# LEDs.net
KiCad netlist of a schematic drawn in Altium Designer
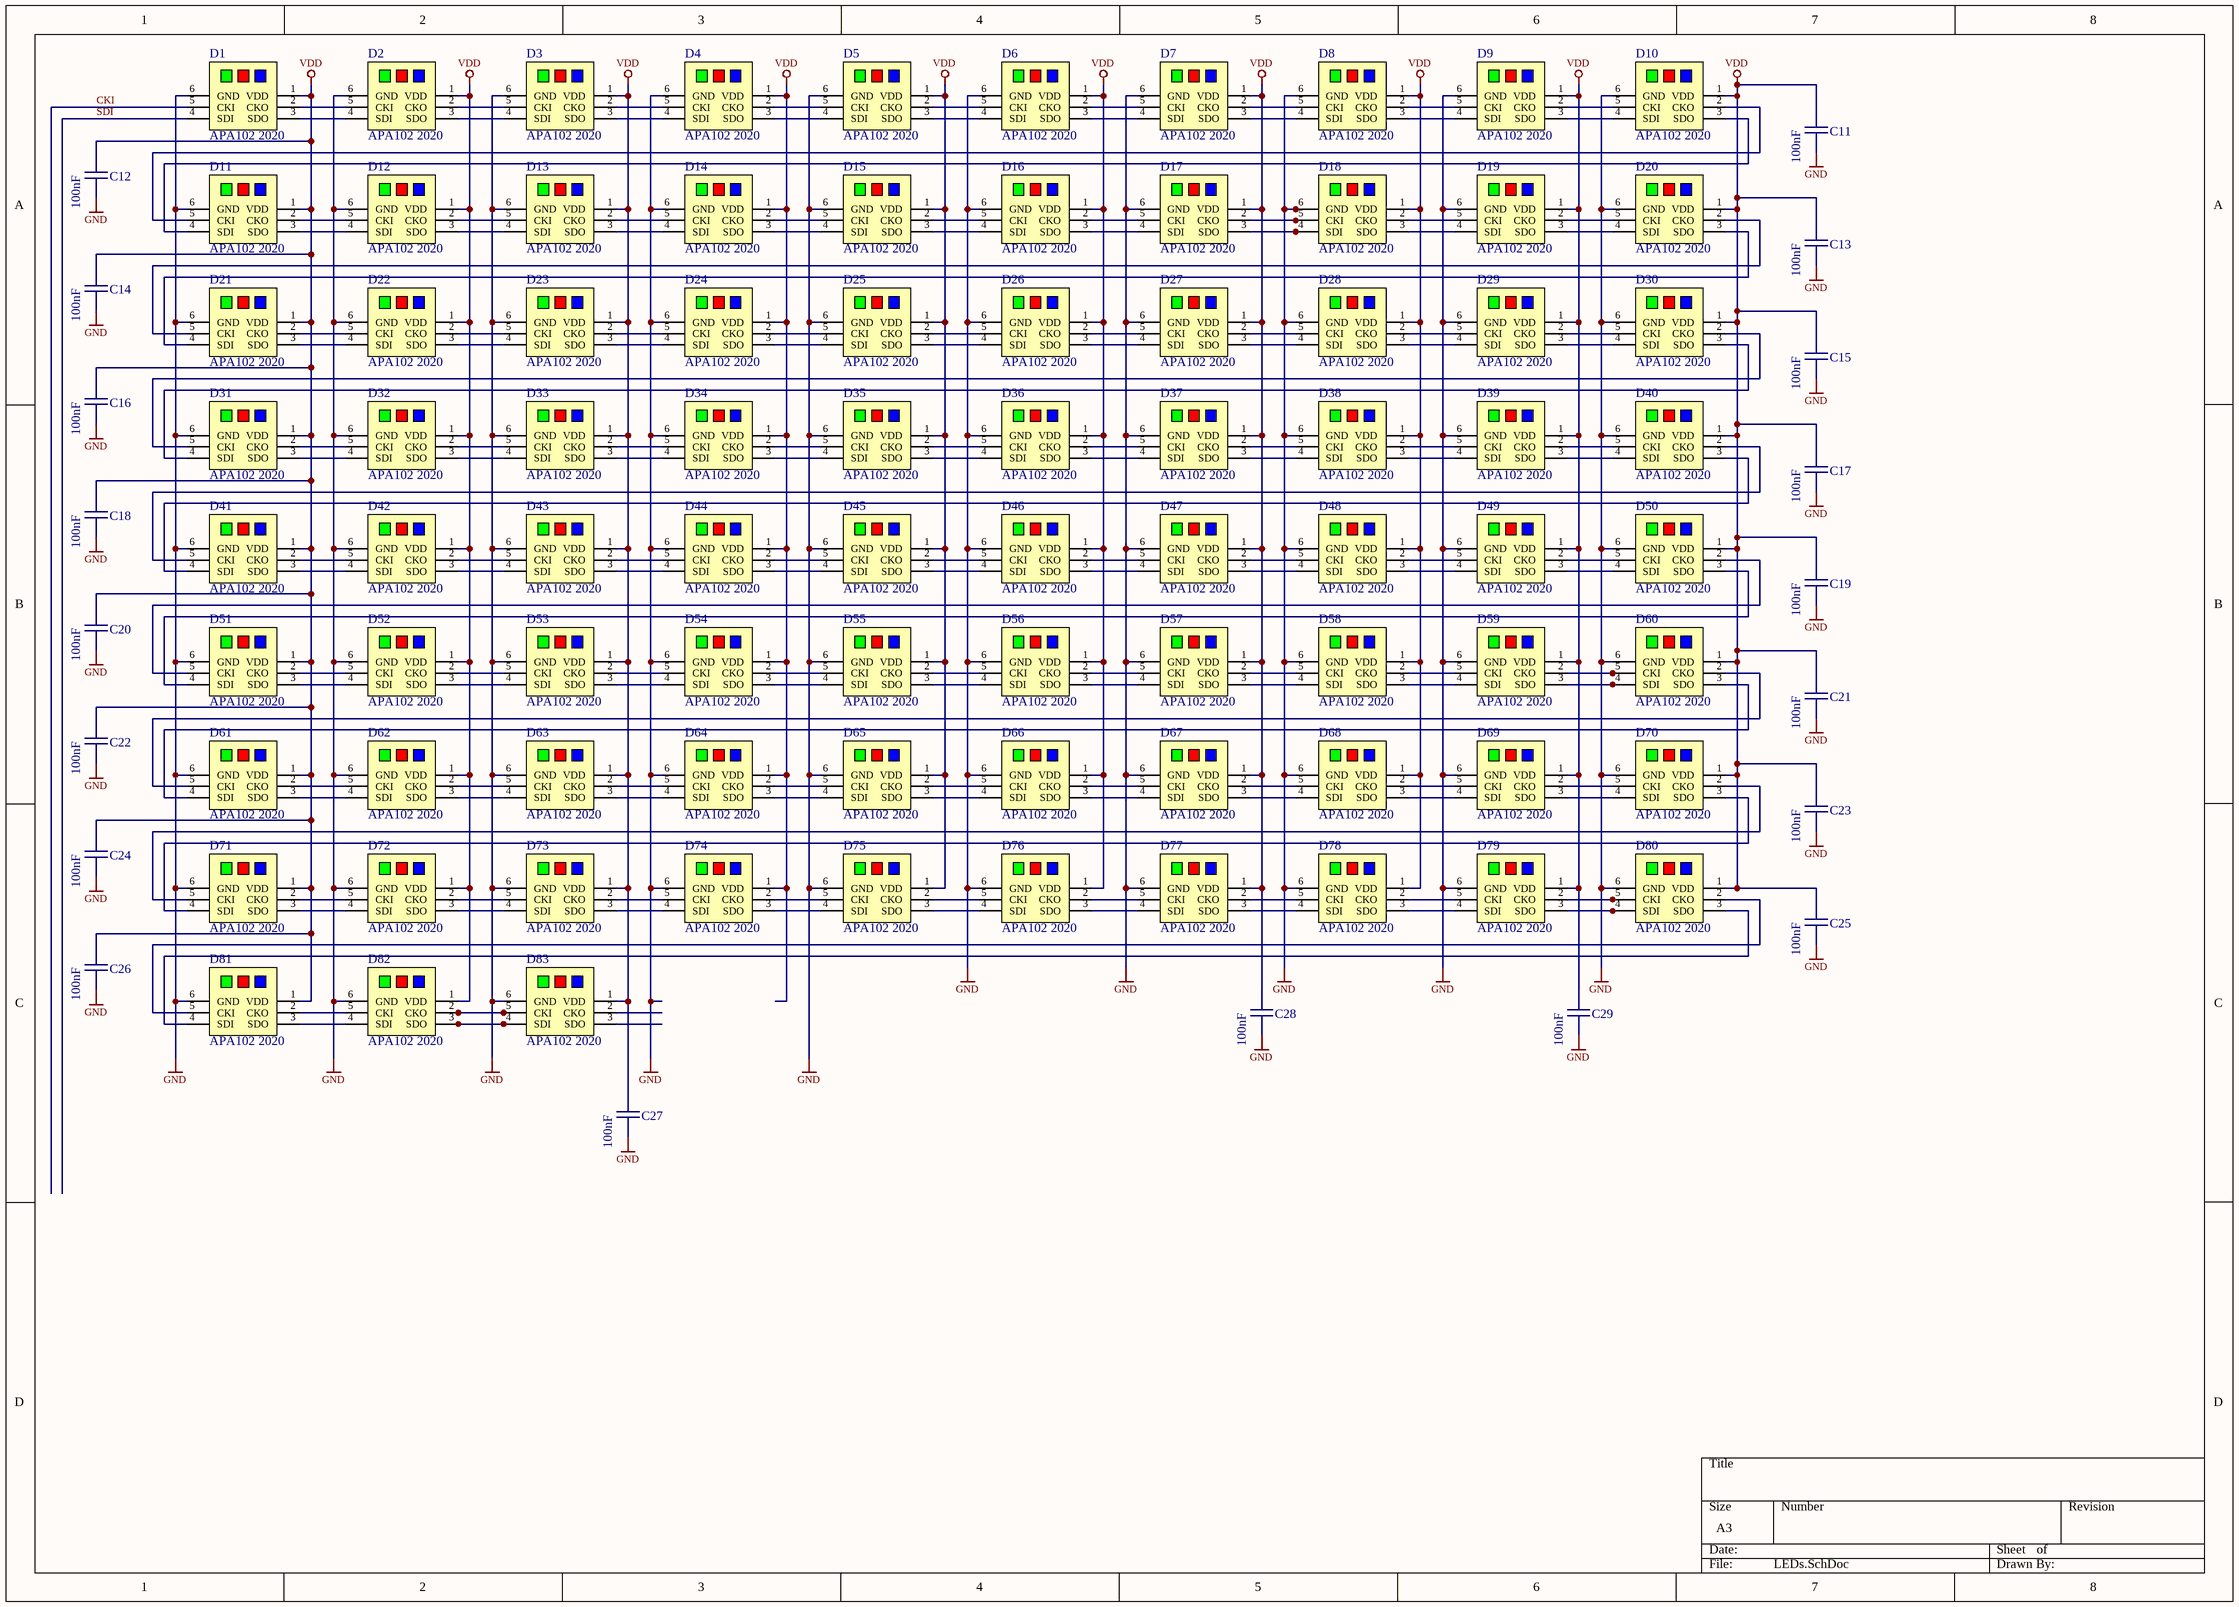
[diagram p0: LEDs.SchDoc]

(export (version "E")
  (design (tool "Eeschema 10.0.6"))
  (components
    (comp (ref "C11")
      (value "100nF")
      (footprint "CAPC0603(1608)55_N")
      (libsource (lib "OVLib_64") (part "CAP"))
    )
    (comp (ref "C12")
      (value "100nF")
      (footprint "CAPC0603(1608)55_N")
      (libsource (lib "OVLib_64") (part "CAP"))
    )
    (comp (ref "C13")
      (value "100nF")
      (footprint "CAPC0603(1608)55_N")
      (libsource (lib "OVLib_64") (part "CAP"))
    )
    (comp (ref "C14")
      (value "100nF")
      (footprint "CAPC0603(1608)55_N")
      (libsource (lib "OVLib_64") (part "CAP"))
    )
    (comp (ref "C15")
      (value "100nF")
      (footprint "CAPC0603(1608)55_N")
      (libsource (lib "OVLib_64") (part "CAP"))
    )
    (comp (ref "C16")
      (value "100nF")
      (footprint "CAPC0603(1608)55_N")
      (libsource (lib "OVLib_64") (part "CAP"))
    )
    (comp (ref "C17")
      (value "100nF")
      (footprint "CAPC0603(1608)55_N")
      (libsource (lib "OVLib_64") (part "CAP"))
    )
    (comp (ref "C18")
      (value "100nF")
      (footprint "CAPC0603(1608)55_N")
      (libsource (lib "OVLib_64") (part "CAP"))
    )
    (comp (ref "C19")
      (value "100nF")
      (footprint "CAPC0603(1608)55_N")
      (libsource (lib "OVLib_64") (part "CAP"))
    )
    (comp (ref "C20")
      (value "100nF")
      (footprint "CAPC0603(1608)55_N")
      (libsource (lib "OVLib_64") (part "CAP"))
    )
    (comp (ref "C21")
      (value "100nF")
      (footprint "CAPC0603(1608)55_N")
      (libsource (lib "OVLib_64") (part "CAP"))
    )
    (comp (ref "C22")
      (value "100nF")
      (footprint "CAPC0603(1608)55_N")
      (libsource (lib "OVLib_64") (part "CAP"))
    )
    (comp (ref "C23")
      (value "100nF")
      (footprint "CAPC0603(1608)55_N")
      (libsource (lib "OVLib_64") (part "CAP"))
    )
    (comp (ref "C24")
      (value "100nF")
      (footprint "CAPC0603(1608)55_N")
      (libsource (lib "OVLib_64") (part "CAP"))
    )
    (comp (ref "C25")
      (value "100nF")
      (footprint "CAPC0603(1608)55_N")
      (libsource (lib "OVLib_64") (part "CAP"))
    )
    (comp (ref "C26")
      (value "100nF")
      (footprint "CAPC0603(1608)55_N")
      (libsource (lib "OVLib_64") (part "CAP"))
    )
    (comp (ref "C27")
      (value "100nF")
      (footprint "CAPC0603(1608)55_N")
      (libsource (lib "OVLib_64") (part "CAP"))
    )
    (comp (ref "C28")
      (value "100nF")
      (footprint "CAPC0603(1608)55_N")
      (libsource (lib "OVLib_64") (part "CAP"))
    )
    (comp (ref "C29")
      (value "100nF")
      (footprint "CAPC0603(1608)55_N")
      (libsource (lib "OVLib_64") (part "CAP"))
    )
    (comp (ref "D1")
      (value "APA102 2020")
      (footprint "APA_RGB_LED_2020")
      (libsource (lib "OVLib_64") (part "LED_RGB_APA102"))
    )
    (comp (ref "D2")
      (value "APA102 2020")
      (footprint "APA_RGB_LED_2020")
      (libsource (lib "OVLib_64") (part "LED_RGB_APA102"))
    )
    (comp (ref "D3")
      (value "APA102 2020")
      (footprint "APA_RGB_LED_2020")
      (libsource (lib "OVLib_64") (part "LED_RGB_APA102"))
    )
    (comp (ref "D4")
      (value "APA102 2020")
      (footprint "APA_RGB_LED_2020")
      (libsource (lib "OVLib_64") (part "LED_RGB_APA102"))
    )
    (comp (ref "D5")
      (value "APA102 2020")
      (footprint "APA_RGB_LED_2020")
      (libsource (lib "OVLib_64") (part "LED_RGB_APA102"))
    )
    (comp (ref "D6")
      (value "APA102 2020")
      (footprint "APA_RGB_LED_2020")
      (libsource (lib "OVLib_64") (part "LED_RGB_APA102"))
    )
    (comp (ref "D7")
      (value "APA102 2020")
      (footprint "APA_RGB_LED_2020")
      (libsource (lib "OVLib_64") (part "LED_RGB_APA102"))
    )
    (comp (ref "D8")
      (value "APA102 2020")
      (footprint "APA_RGB_LED_2020")
      (libsource (lib "OVLib_64") (part "LED_RGB_APA102"))
    )
    (comp (ref "D9")
      (value "APA102 2020")
      (footprint "APA_RGB_LED_2020")
      (libsource (lib "OVLib_64") (part "LED_RGB_APA102"))
    )
    (comp (ref "D10")
      (value "APA102 2020")
      (footprint "APA_RGB_LED_2020")
      (libsource (lib "OVLib_64") (part "LED_RGB_APA102"))
    )
    (comp (ref "D11")
      (value "APA102 2020")
      (footprint "APA_RGB_LED_2020")
      (libsource (lib "OVLib_64") (part "LED_RGB_APA102"))
    )
    (comp (ref "D12")
      (value "APA102 2020")
      (footprint "APA_RGB_LED_2020")
      (libsource (lib "OVLib_64") (part "LED_RGB_APA102"))
    )
    (comp (ref "D13")
      (value "APA102 2020")
      (footprint "APA_RGB_LED_2020")
      (libsource (lib "OVLib_64") (part "LED_RGB_APA102"))
    )
    (comp (ref "D14")
      (value "APA102 2020")
      (footprint "APA_RGB_LED_2020")
      (libsource (lib "OVLib_64") (part "LED_RGB_APA102"))
    )
    (comp (ref "D15")
      (value "APA102 2020")
      (footprint "APA_RGB_LED_2020")
      (libsource (lib "OVLib_64") (part "LED_RGB_APA102"))
    )
    (comp (ref "D16")
      (value "APA102 2020")
      (footprint "APA_RGB_LED_2020")
      (libsource (lib "OVLib_64") (part "LED_RGB_APA102"))
    )
    (comp (ref "D17")
      (value "APA102 2020")
      (footprint "APA_RGB_LED_2020")
      (libsource (lib "OVLib_64") (part "LED_RGB_APA102"))
    )
    (comp (ref "D18")
      (value "APA102 2020")
      (footprint "APA_RGB_LED_2020")
      (libsource (lib "OVLib_64") (part "LED_RGB_APA102"))
    )
    (comp (ref "D19")
      (value "APA102 2020")
      (footprint "APA_RGB_LED_2020")
      (libsource (lib "OVLib_64") (part "LED_RGB_APA102"))
    )
    (comp (ref "D20")
      (value "APA102 2020")
      (footprint "APA_RGB_LED_2020")
      (libsource (lib "OVLib_64") (part "LED_RGB_APA102"))
    )
    (comp (ref "D21")
      (value "APA102 2020")
      (footprint "APA_RGB_LED_2020")
      (libsource (lib "OVLib_64") (part "LED_RGB_APA102"))
    )
    (comp (ref "D22")
      (value "APA102 2020")
      (footprint "APA_RGB_LED_2020")
      (libsource (lib "OVLib_64") (part "LED_RGB_APA102"))
    )
    (comp (ref "D23")
      (value "APA102 2020")
      (footprint "APA_RGB_LED_2020")
      (libsource (lib "OVLib_64") (part "LED_RGB_APA102"))
    )
    (comp (ref "D24")
      (value "APA102 2020")
      (footprint "APA_RGB_LED_2020")
      (libsource (lib "OVLib_64") (part "LED_RGB_APA102"))
    )
    (comp (ref "D25")
      (value "APA102 2020")
      (footprint "APA_RGB_LED_2020")
      (libsource (lib "OVLib_64") (part "LED_RGB_APA102"))
    )
    (comp (ref "D26")
      (value "APA102 2020")
      (footprint "APA_RGB_LED_2020")
      (libsource (lib "OVLib_64") (part "LED_RGB_APA102"))
    )
    (comp (ref "D27")
      (value "APA102 2020")
      (footprint "APA_RGB_LED_2020")
      (libsource (lib "OVLib_64") (part "LED_RGB_APA102"))
    )
    (comp (ref "D28")
      (value "APA102 2020")
      (footprint "APA_RGB_LED_2020")
      (libsource (lib "OVLib_64") (part "LED_RGB_APA102"))
    )
    (comp (ref "D29")
      (value "APA102 2020")
      (footprint "APA_RGB_LED_2020")
      (libsource (lib "OVLib_64") (part "LED_RGB_APA102"))
    )
    (comp (ref "D30")
      (value "APA102 2020")
      (footprint "APA_RGB_LED_2020")
      (libsource (lib "OVLib_64") (part "LED_RGB_APA102"))
    )
    (comp (ref "D31")
      (value "APA102 2020")
      (footprint "APA_RGB_LED_2020")
      (libsource (lib "OVLib_64") (part "LED_RGB_APA102"))
    )
    (comp (ref "D32")
      (value "APA102 2020")
      (footprint "APA_RGB_LED_2020")
      (libsource (lib "OVLib_64") (part "LED_RGB_APA102"))
    )
    (comp (ref "D33")
      (value "APA102 2020")
      (footprint "APA_RGB_LED_2020")
      (libsource (lib "OVLib_64") (part "LED_RGB_APA102"))
    )
    (comp (ref "D34")
      (value "APA102 2020")
      (footprint "APA_RGB_LED_2020")
      (libsource (lib "OVLib_64") (part "LED_RGB_APA102"))
    )
    (comp (ref "D35")
      (value "APA102 2020")
      (footprint "APA_RGB_LED_2020")
      (libsource (lib "OVLib_64") (part "LED_RGB_APA102"))
    )
    (comp (ref "D36")
      (value "APA102 2020")
      (footprint "APA_RGB_LED_2020")
      (libsource (lib "OVLib_64") (part "LED_RGB_APA102"))
    )
    (comp (ref "D37")
      (value "APA102 2020")
      (footprint "APA_RGB_LED_2020")
      (libsource (lib "OVLib_64") (part "LED_RGB_APA102"))
    )
    (comp (ref "D38")
      (value "APA102 2020")
      (footprint "APA_RGB_LED_2020")
      (libsource (lib "OVLib_64") (part "LED_RGB_APA102"))
    )
    (comp (ref "D39")
      (value "APA102 2020")
      (footprint "APA_RGB_LED_2020")
      (libsource (lib "OVLib_64") (part "LED_RGB_APA102"))
    )
    (comp (ref "D40")
      (value "APA102 2020")
      (footprint "APA_RGB_LED_2020")
      (libsource (lib "OVLib_64") (part "LED_RGB_APA102"))
    )
    (comp (ref "D41")
      (value "APA102 2020")
      (footprint "APA_RGB_LED_2020")
      (libsource (lib "OVLib_64") (part "LED_RGB_APA102"))
    )
    (comp (ref "D42")
      (value "APA102 2020")
      (footprint "APA_RGB_LED_2020")
      (libsource (lib "OVLib_64") (part "LED_RGB_APA102"))
    )
    (comp (ref "D43")
      (value "APA102 2020")
      (footprint "APA_RGB_LED_2020")
      (libsource (lib "OVLib_64") (part "LED_RGB_APA102"))
    )
    (comp (ref "D44")
      (value "APA102 2020")
      (footprint "APA_RGB_LED_2020")
      (libsource (lib "OVLib_64") (part "LED_RGB_APA102"))
    )
    (comp (ref "D45")
      (value "APA102 2020")
      (footprint "APA_RGB_LED_2020")
      (libsource (lib "OVLib_64") (part "LED_RGB_APA102"))
    )
    (comp (ref "D46")
      (value "APA102 2020")
      (footprint "APA_RGB_LED_2020")
      (libsource (lib "OVLib_64") (part "LED_RGB_APA102"))
    )
    (comp (ref "D47")
      (value "APA102 2020")
      (footprint "APA_RGB_LED_2020")
      (libsource (lib "OVLib_64") (part "LED_RGB_APA102"))
    )
    (comp (ref "D48")
      (value "APA102 2020")
      (footprint "APA_RGB_LED_2020")
      (libsource (lib "OVLib_64") (part "LED_RGB_APA102"))
    )
    (comp (ref "D49")
      (value "APA102 2020")
      (footprint "APA_RGB_LED_2020")
      (libsource (lib "OVLib_64") (part "LED_RGB_APA102"))
    )
    (comp (ref "D50")
      (value "APA102 2020")
      (footprint "APA_RGB_LED_2020")
      (libsource (lib "OVLib_64") (part "LED_RGB_APA102"))
    )
    (comp (ref "D51")
      (value "APA102 2020")
      (footprint "APA_RGB_LED_2020")
      (libsource (lib "OVLib_64") (part "LED_RGB_APA102"))
    )
    (comp (ref "D52")
      (value "APA102 2020")
      (footprint "APA_RGB_LED_2020")
      (libsource (lib "OVLib_64") (part "LED_RGB_APA102"))
    )
    (comp (ref "D53")
      (value "APA102 2020")
      (footprint "APA_RGB_LED_2020")
      (libsource (lib "OVLib_64") (part "LED_RGB_APA102"))
    )
    (comp (ref "D54")
      (value "APA102 2020")
      (footprint "APA_RGB_LED_2020")
      (libsource (lib "OVLib_64") (part "LED_RGB_APA102"))
    )
    (comp (ref "D55")
      (value "APA102 2020")
      (footprint "APA_RGB_LED_2020")
      (libsource (lib "OVLib_64") (part "LED_RGB_APA102"))
    )
    (comp (ref "D56")
      (value "APA102 2020")
      (footprint "APA_RGB_LED_2020")
      (libsource (lib "OVLib_64") (part "LED_RGB_APA102"))
    )
    (comp (ref "D57")
      (value "APA102 2020")
      (footprint "APA_RGB_LED_2020")
      (libsource (lib "OVLib_64") (part "LED_RGB_APA102"))
    )
    (comp (ref "D58")
      (value "APA102 2020")
      (footprint "APA_RGB_LED_2020")
      (libsource (lib "OVLib_64") (part "LED_RGB_APA102"))
    )
    (comp (ref "D59")
      (value "APA102 2020")
      (footprint "APA_RGB_LED_2020")
      (libsource (lib "OVLib_64") (part "LED_RGB_APA102"))
    )
    (comp (ref "D60")
      (value "APA102 2020")
      (footprint "APA_RGB_LED_2020")
      (libsource (lib "OVLib_64") (part "LED_RGB_APA102"))
    )
    (comp (ref "D61")
      (value "APA102 2020")
      (footprint "APA_RGB_LED_2020")
      (libsource (lib "OVLib_64") (part "LED_RGB_APA102"))
    )
    (comp (ref "D62")
      (value "APA102 2020")
      (footprint "APA_RGB_LED_2020")
      (libsource (lib "OVLib_64") (part "LED_RGB_APA102"))
    )
    (comp (ref "D63")
      (value "APA102 2020")
      (footprint "APA_RGB_LED_2020")
      (libsource (lib "OVLib_64") (part "LED_RGB_APA102"))
    )
    (comp (ref "D64")
      (value "APA102 2020")
      (footprint "APA_RGB_LED_2020")
      (libsource (lib "OVLib_64") (part "LED_RGB_APA102"))
    )
    (comp (ref "D65")
      (value "APA102 2020")
      (footprint "APA_RGB_LED_2020")
      (libsource (lib "OVLib_64") (part "LED_RGB_APA102"))
    )
    (comp (ref "D66")
      (value "APA102 2020")
      (footprint "APA_RGB_LED_2020")
      (libsource (lib "OVLib_64") (part "LED_RGB_APA102"))
    )
    (comp (ref "D67")
      (value "APA102 2020")
      (footprint "APA_RGB_LED_2020")
      (libsource (lib "OVLib_64") (part "LED_RGB_APA102"))
    )
    (comp (ref "D68")
      (value "APA102 2020")
      (footprint "APA_RGB_LED_2020")
      (libsource (lib "OVLib_64") (part "LED_RGB_APA102"))
    )
    (comp (ref "D69")
      (value "APA102 2020")
      (footprint "APA_RGB_LED_2020")
      (libsource (lib "OVLib_64") (part "LED_RGB_APA102"))
    )
    (comp (ref "D70")
      (value "APA102 2020")
      (footprint "APA_RGB_LED_2020")
      (libsource (lib "OVLib_64") (part "LED_RGB_APA102"))
    )
    (comp (ref "D71")
      (value "APA102 2020")
      (footprint "APA_RGB_LED_2020")
      (libsource (lib "OVLib_64") (part "LED_RGB_APA102"))
    )
    (comp (ref "D72")
      (value "APA102 2020")
      (footprint "APA_RGB_LED_2020")
      (libsource (lib "OVLib_64") (part "LED_RGB_APA102"))
    )
    (comp (ref "D73")
      (value "APA102 2020")
      (footprint "APA_RGB_LED_2020")
      (libsource (lib "OVLib_64") (part "LED_RGB_APA102"))
    )
    (comp (ref "D74")
      (value "APA102 2020")
      (footprint "APA_RGB_LED_2020")
      (libsource (lib "OVLib_64") (part "LED_RGB_APA102"))
    )
    (comp (ref "D75")
      (value "APA102 2020")
      (footprint "APA_RGB_LED_2020")
      (libsource (lib "OVLib_64") (part "LED_RGB_APA102"))
    )
    (comp (ref "D76")
      (value "APA102 2020")
      (footprint "APA_RGB_LED_2020")
      (libsource (lib "OVLib_64") (part "LED_RGB_APA102"))
    )
    (comp (ref "D77")
      (value "APA102 2020")
      (footprint "APA_RGB_LED_2020")
      (libsource (lib "OVLib_64") (part "LED_RGB_APA102"))
    )
    (comp (ref "D78")
      (value "APA102 2020")
      (footprint "APA_RGB_LED_2020")
      (libsource (lib "OVLib_64") (part "LED_RGB_APA102"))
    )
    (comp (ref "D79")
      (value "APA102 2020")
      (footprint "APA_RGB_LED_2020")
      (libsource (lib "OVLib_64") (part "LED_RGB_APA102"))
    )
    (comp (ref "D80")
      (value "APA102 2020")
      (footprint "APA_RGB_LED_2020")
      (libsource (lib "OVLib_64") (part "LED_RGB_APA102"))
    )
    (comp (ref "D81")
      (value "APA102 2020")
      (footprint "APA_RGB_LED_2020")
      (libsource (lib "OVLib_64") (part "LED_RGB_APA102"))
    )
    (comp (ref "D82")
      (value "APA102 2020")
      (footprint "APA_RGB_LED_2020")
      (libsource (lib "OVLib_64") (part "LED_RGB_APA102"))
    )
    (comp (ref "D83")
      (value "APA102 2020")
      (footprint "APA_RGB_LED_2020")
      (libsource (lib "OVLib_64") (part "LED_RGB_APA102"))
    )
  )
  (nets
    (net (code "1") (name "/CKI") (class "Default")
      (node (ref "D1") (pin "5") (pinfunction "CKI_5") (pintype "passive"))
    )
    (net (code "2") (name "/SDI") (class "Default")
      (node (ref "D1") (pin "4") (pinfunction "SDI_4") (pintype "passive"))
    )
    (net (code "3") (name "GND") (class "Default")
      (node (ref "C11") (pin "1") (pinfunction "1_1") (pintype "passive"))
      (node (ref "C12") (pin "1") (pinfunction "1_1") (pintype "passive"))
      (node (ref "C13") (pin "1") (pinfunction "1_1") (pintype "passive"))
      (node (ref "C14") (pin "1") (pinfunction "1_1") (pintype "passive"))
      (node (ref "C15") (pin "1") (pinfunction "1_1") (pintype "passive"))
      (node (ref "C16") (pin "1") (pinfunction "1_1") (pintype "passive"))
      (node (ref "C17") (pin "1") (pinfunction "1_1") (pintype "passive"))
      (node (ref "C18") (pin "1") (pinfunction "1_1") (pintype "passive"))
      (node (ref "C19") (pin "1") (pinfunction "1_1") (pintype "passive"))
      (node (ref "C20") (pin "1") (pinfunction "1_1") (pintype "passive"))
      (node (ref "C21") (pin "1") (pinfunction "1_1") (pintype "passive"))
      (node (ref "C22") (pin "1") (pinfunction "1_1") (pintype "passive"))
      (node (ref "C23") (pin "1") (pinfunction "1_1") (pintype "passive"))
      (node (ref "C24") (pin "1") (pinfunction "1_1") (pintype "passive"))
      (node (ref "C25") (pin "1") (pinfunction "1_1") (pintype "passive"))
      (node (ref "C26") (pin "1") (pinfunction "1_1") (pintype "passive"))
      (node (ref "C27") (pin "1") (pinfunction "1_1") (pintype "passive"))
      (node (ref "C28") (pin "1") (pinfunction "1_1") (pintype "passive"))
      (node (ref "C29") (pin "1") (pinfunction "1_1") (pintype "passive"))
      (node (ref "D1") (pin "6") (pinfunction "GND_6") (pintype "passive"))
      (node (ref "D10") (pin "6") (pinfunction "GND_6") (pintype "passive"))
      (node (ref "D11") (pin "6") (pinfunction "GND_6") (pintype "passive"))
      (node (ref "D12") (pin "6") (pinfunction "GND_6") (pintype "passive"))
      (node (ref "D13") (pin "6") (pinfunction "GND_6") (pintype "passive"))
      (node (ref "D14") (pin "6") (pinfunction "GND_6") (pintype "passive"))
      (node (ref "D15") (pin "6") (pinfunction "GND_6") (pintype "passive"))
      (node (ref "D16") (pin "6") (pinfunction "GND_6") (pintype "passive"))
      (node (ref "D17") (pin "6") (pinfunction "GND_6") (pintype "passive"))
      (node (ref "D18") (pin "6") (pinfunction "GND_6") (pintype "passive"))
      (node (ref "D19") (pin "6") (pinfunction "GND_6") (pintype "passive"))
      (node (ref "D2") (pin "6") (pinfunction "GND_6") (pintype "passive"))
      (node (ref "D20") (pin "6") (pinfunction "GND_6") (pintype "passive"))
      (node (ref "D21") (pin "6") (pinfunction "GND_6") (pintype "passive"))
      (node (ref "D22") (pin "6") (pinfunction "GND_6") (pintype "passive"))
      (node (ref "D23") (pin "6") (pinfunction "GND_6") (pintype "passive"))
      (node (ref "D24") (pin "6") (pinfunction "GND_6") (pintype "passive"))
      (node (ref "D25") (pin "6") (pinfunction "GND_6") (pintype "passive"))
      (node (ref "D26") (pin "6") (pinfunction "GND_6") (pintype "passive"))
      (node (ref "D27") (pin "6") (pinfunction "GND_6") (pintype "passive"))
      (node (ref "D28") (pin "6") (pinfunction "GND_6") (pintype "passive"))
      (node (ref "D29") (pin "6") (pinfunction "GND_6") (pintype "passive"))
      (node (ref "D3") (pin "6") (pinfunction "GND_6") (pintype "passive"))
      (node (ref "D30") (pin "6") (pinfunction "GND_6") (pintype "passive"))
      (node (ref "D31") (pin "6") (pinfunction "GND_6") (pintype "passive"))
      (node (ref "D32") (pin "6") (pinfunction "GND_6") (pintype "passive"))
      (node (ref "D33") (pin "6") (pinfunction "GND_6") (pintype "passive"))
      (node (ref "D34") (pin "6") (pinfunction "GND_6") (pintype "passive"))
      (node (ref "D35") (pin "6") (pinfunction "GND_6") (pintype "passive"))
      (node (ref "D36") (pin "6") (pinfunction "GND_6") (pintype "passive"))
      (node (ref "D37") (pin "6") (pinfunction "GND_6") (pintype "passive"))
      (node (ref "D38") (pin "6") (pinfunction "GND_6") (pintype "passive"))
      (node (ref "D39") (pin "6") (pinfunction "GND_6") (pintype "passive"))
      (node (ref "D4") (pin "6") (pinfunction "GND_6") (pintype "passive"))
      (node (ref "D40") (pin "6") (pinfunction "GND_6") (pintype "passive"))
      (node (ref "D41") (pin "6") (pinfunction "GND_6") (pintype "passive"))
      (node (ref "D42") (pin "6") (pinfunction "GND_6") (pintype "passive"))
      (node (ref "D43") (pin "6") (pinfunction "GND_6") (pintype "passive"))
      (node (ref "D44") (pin "6") (pinfunction "GND_6") (pintype "passive"))
      (node (ref "D45") (pin "6") (pinfunction "GND_6") (pintype "passive"))
      (node (ref "D46") (pin "6") (pinfunction "GND_6") (pintype "passive"))
      (node (ref "D47") (pin "6") (pinfunction "GND_6") (pintype "passive"))
      (node (ref "D48") (pin "6") (pinfunction "GND_6") (pintype "passive"))
      (node (ref "D49") (pin "6") (pinfunction "GND_6") (pintype "passive"))
      (node (ref "D5") (pin "6") (pinfunction "GND_6") (pintype "passive"))
      (node (ref "D50") (pin "6") (pinfunction "GND_6") (pintype "passive"))
      (node (ref "D51") (pin "6") (pinfunction "GND_6") (pintype "passive"))
      (node (ref "D52") (pin "6") (pinfunction "GND_6") (pintype "passive"))
      (node (ref "D53") (pin "6") (pinfunction "GND_6") (pintype "passive"))
      (node (ref "D54") (pin "6") (pinfunction "GND_6") (pintype "passive"))
      (node (ref "D55") (pin "6") (pinfunction "GND_6") (pintype "passive"))
      (node (ref "D56") (pin "6") (pinfunction "GND_6") (pintype "passive"))
      (node (ref "D57") (pin "6") (pinfunction "GND_6") (pintype "passive"))
      (node (ref "D58") (pin "6") (pinfunction "GND_6") (pintype "passive"))
      (node (ref "D59") (pin "6") (pinfunction "GND_6") (pintype "passive"))
      (node (ref "D6") (pin "6") (pinfunction "GND_6") (pintype "passive"))
      (node (ref "D60") (pin "6") (pinfunction "GND_6") (pintype "passive"))
      (node (ref "D61") (pin "6") (pinfunction "GND_6") (pintype "passive"))
      (node (ref "D62") (pin "6") (pinfunction "GND_6") (pintype "passive"))
      (node (ref "D63") (pin "6") (pinfunction "GND_6") (pintype "passive"))
      (node (ref "D64") (pin "6") (pinfunction "GND_6") (pintype "passive"))
      (node (ref "D65") (pin "6") (pinfunction "GND_6") (pintype "passive"))
      (node (ref "D66") (pin "6") (pinfunction "GND_6") (pintype "passive"))
      (node (ref "D67") (pin "6") (pinfunction "GND_6") (pintype "passive"))
      (node (ref "D68") (pin "6") (pinfunction "GND_6") (pintype "passive"))
      (node (ref "D69") (pin "6") (pinfunction "GND_6") (pintype "passive"))
      (node (ref "D7") (pin "6") (pinfunction "GND_6") (pintype "passive"))
      (node (ref "D70") (pin "6") (pinfunction "GND_6") (pintype "passive"))
      (node (ref "D71") (pin "6") (pinfunction "GND_6") (pintype "passive"))
      (node (ref "D72") (pin "6") (pinfunction "GND_6") (pintype "passive"))
      (node (ref "D73") (pin "6") (pinfunction "GND_6") (pintype "passive"))
      (node (ref "D74") (pin "6") (pinfunction "GND_6") (pintype "passive"))
      (node (ref "D75") (pin "6") (pinfunction "GND_6") (pintype "passive"))
      (node (ref "D76") (pin "6") (pinfunction "GND_6") (pintype "passive"))
      (node (ref "D77") (pin "6") (pinfunction "GND_6") (pintype "passive"))
      (node (ref "D78") (pin "6") (pinfunction "GND_6") (pintype "passive"))
      (node (ref "D79") (pin "6") (pinfunction "GND_6") (pintype "passive"))
      (node (ref "D8") (pin "6") (pinfunction "GND_6") (pintype "passive"))
      (node (ref "D80") (pin "6") (pinfunction "GND_6") (pintype "passive"))
      (node (ref "D81") (pin "6") (pinfunction "GND_6") (pintype "passive"))
      (node (ref "D82") (pin "6") (pinfunction "GND_6") (pintype "passive"))
      (node (ref "D83") (pin "6") (pinfunction "GND_6") (pintype "passive"))
      (node (ref "D9") (pin "6") (pinfunction "GND_6") (pintype "passive"))
    )
    (net (code "4") (name "Net-(D1-CKO)") (class "Default")
      (node (ref "D1") (pin "2") (pinfunction "CKO_2") (pintype "passive"))
      (node (ref "D2") (pin "5") (pinfunction "CKI_5") (pintype "passive"))
    )
    (net (code "5") (name "Net-(D1-SDO)") (class "Default")
      (node (ref "D1") (pin "3") (pinfunction "SDO_3") (pintype "passive"))
      (node (ref "D2") (pin "4") (pinfunction "SDI_4") (pintype "passive"))
    )
    (net (code "6") (name "Net-(D2-CKO)") (class "Default")
      (node (ref "D2") (pin "2") (pinfunction "CKO_2") (pintype "passive"))
      (node (ref "D3") (pin "5") (pinfunction "CKI_5") (pintype "passive"))
    )
    (net (code "7") (name "Net-(D2-SDO)") (class "Default")
      (node (ref "D2") (pin "3") (pinfunction "SDO_3") (pintype "passive"))
      (node (ref "D3") (pin "4") (pinfunction "SDI_4") (pintype "passive"))
    )
    (net (code "8") (name "Net-(D3-CKO)") (class "Default")
      (node (ref "D3") (pin "2") (pinfunction "CKO_2") (pintype "passive"))
      (node (ref "D4") (pin "5") (pinfunction "CKI_5") (pintype "passive"))
    )
    (net (code "9") (name "Net-(D3-SDO)") (class "Default")
      (node (ref "D3") (pin "3") (pinfunction "SDO_3") (pintype "passive"))
      (node (ref "D4") (pin "4") (pinfunction "SDI_4") (pintype "passive"))
    )
    (net (code "10") (name "Net-(D4-CKO)") (class "Default")
      (node (ref "D4") (pin "2") (pinfunction "CKO_2") (pintype "passive"))
      (node (ref "D5") (pin "5") (pinfunction "CKI_5") (pintype "passive"))
    )
    (net (code "11") (name "Net-(D4-SDO)") (class "Default")
      (node (ref "D4") (pin "3") (pinfunction "SDO_3") (pintype "passive"))
      (node (ref "D5") (pin "4") (pinfunction "SDI_4") (pintype "passive"))
    )
    (net (code "12") (name "Net-(D5-CKO)") (class "Default")
      (node (ref "D5") (pin "2") (pinfunction "CKO_2") (pintype "passive"))
      (node (ref "D6") (pin "5") (pinfunction "CKI_5") (pintype "passive"))
    )
    (net (code "13") (name "Net-(D5-SDO)") (class "Default")
      (node (ref "D5") (pin "3") (pinfunction "SDO_3") (pintype "passive"))
      (node (ref "D6") (pin "4") (pinfunction "SDI_4") (pintype "passive"))
    )
    (net (code "14") (name "Net-(D6-CKO)") (class "Default")
      (node (ref "D6") (pin "2") (pinfunction "CKO_2") (pintype "passive"))
      (node (ref "D7") (pin "5") (pinfunction "CKI_5") (pintype "passive"))
    )
    (net (code "15") (name "Net-(D6-SDO)") (class "Default")
      (node (ref "D6") (pin "3") (pinfunction "SDO_3") (pintype "passive"))
      (node (ref "D7") (pin "4") (pinfunction "SDI_4") (pintype "passive"))
    )
    (net (code "16") (name "Net-(D7-CKO)") (class "Default")
      (node (ref "D7") (pin "2") (pinfunction "CKO_2") (pintype "passive"))
      (node (ref "D8") (pin "5") (pinfunction "CKI_5") (pintype "passive"))
    )
    (net (code "17") (name "Net-(D7-SDO)") (class "Default")
      (node (ref "D7") (pin "3") (pinfunction "SDO_3") (pintype "passive"))
      (node (ref "D8") (pin "4") (pinfunction "SDI_4") (pintype "passive"))
    )
    (net (code "18") (name "Net-(D8-CKO)") (class "Default")
      (node (ref "D8") (pin "2") (pinfunction "CKO_2") (pintype "passive"))
      (node (ref "D9") (pin "5") (pinfunction "CKI_5") (pintype "passive"))
    )
    (net (code "19") (name "Net-(D8-SDO)") (class "Default")
      (node (ref "D8") (pin "3") (pinfunction "SDO_3") (pintype "passive"))
      (node (ref "D9") (pin "4") (pinfunction "SDI_4") (pintype "passive"))
    )
    (net (code "20") (name "Net-(D10-CKI)") (class "Default")
      (node (ref "D10") (pin "5") (pinfunction "CKI_5") (pintype "passive"))
      (node (ref "D9") (pin "2") (pinfunction "CKO_2") (pintype "passive"))
    )
    (net (code "21") (name "Net-(D10-CKO)") (class "Default")
      (node (ref "D10") (pin "2") (pinfunction "CKO_2") (pintype "passive"))
      (node (ref "D11") (pin "5") (pinfunction "CKI_5") (pintype "passive"))
    )
    (net (code "22") (name "Net-(D10-SDI)") (class "Default")
      (node (ref "D10") (pin "4") (pinfunction "SDI_4") (pintype "passive"))
      (node (ref "D9") (pin "3") (pinfunction "SDO_3") (pintype "passive"))
    )
    (net (code "23") (name "Net-(D10-SDO)") (class "Default")
      (node (ref "D10") (pin "3") (pinfunction "SDO_3") (pintype "passive"))
      (node (ref "D11") (pin "4") (pinfunction "SDI_4") (pintype "passive"))
    )
    (net (code "24") (name "Net-(D11-CKO)") (class "Default")
      (node (ref "D11") (pin "2") (pinfunction "CKO_2") (pintype "passive"))
      (node (ref "D12") (pin "5") (pinfunction "CKI_5") (pintype "passive"))
    )
    (net (code "25") (name "Net-(D11-SDO)") (class "Default")
      (node (ref "D11") (pin "3") (pinfunction "SDO_3") (pintype "passive"))
      (node (ref "D12") (pin "4") (pinfunction "SDI_4") (pintype "passive"))
    )
    (net (code "26") (name "Net-(D12-CKO)") (class "Default")
      (node (ref "D12") (pin "2") (pinfunction "CKO_2") (pintype "passive"))
      (node (ref "D13") (pin "5") (pinfunction "CKI_5") (pintype "passive"))
    )
    (net (code "27") (name "Net-(D12-SDO)") (class "Default")
      (node (ref "D12") (pin "3") (pinfunction "SDO_3") (pintype "passive"))
      (node (ref "D13") (pin "4") (pinfunction "SDI_4") (pintype "passive"))
    )
    (net (code "28") (name "Net-(D13-CKO)") (class "Default")
      (node (ref "D13") (pin "2") (pinfunction "CKO_2") (pintype "passive"))
      (node (ref "D14") (pin "5") (pinfunction "CKI_5") (pintype "passive"))
    )
    (net (code "29") (name "Net-(D13-SDO)") (class "Default")
      (node (ref "D13") (pin "3") (pinfunction "SDO_3") (pintype "passive"))
      (node (ref "D14") (pin "4") (pinfunction "SDI_4") (pintype "passive"))
    )
    (net (code "30") (name "Net-(D14-CKO)") (class "Default")
      (node (ref "D14") (pin "2") (pinfunction "CKO_2") (pintype "passive"))
      (node (ref "D15") (pin "5") (pinfunction "CKI_5") (pintype "passive"))
    )
    (net (code "31") (name "Net-(D14-SDO)") (class "Default")
      (node (ref "D14") (pin "3") (pinfunction "SDO_3") (pintype "passive"))
      (node (ref "D15") (pin "4") (pinfunction "SDI_4") (pintype "passive"))
    )
    (net (code "32") (name "Net-(D15-CKO)") (class "Default")
      (node (ref "D15") (pin "2") (pinfunction "CKO_2") (pintype "passive"))
      (node (ref "D16") (pin "5") (pinfunction "CKI_5") (pintype "passive"))
    )
    (net (code "33") (name "Net-(D15-SDO)") (class "Default")
      (node (ref "D15") (pin "3") (pinfunction "SDO_3") (pintype "passive"))
      (node (ref "D16") (pin "4") (pinfunction "SDI_4") (pintype "passive"))
    )
    (net (code "34") (name "Net-(D16-CKO)") (class "Default")
      (node (ref "D16") (pin "2") (pinfunction "CKO_2") (pintype "passive"))
      (node (ref "D17") (pin "5") (pinfunction "CKI_5") (pintype "passive"))
    )
    (net (code "35") (name "Net-(D16-SDO)") (class "Default")
      (node (ref "D16") (pin "3") (pinfunction "SDO_3") (pintype "passive"))
      (node (ref "D17") (pin "4") (pinfunction "SDI_4") (pintype "passive"))
    )
    (net (code "36") (name "Net-(D17-CKO)") (class "Default")
      (node (ref "D17") (pin "2") (pinfunction "CKO_2") (pintype "passive"))
      (node (ref "D18") (pin "5") (pinfunction "CKI_5") (pintype "passive"))
    )
    (net (code "37") (name "Net-(D17-SDO)") (class "Default")
      (node (ref "D17") (pin "3") (pinfunction "SDO_3") (pintype "passive"))
      (node (ref "D18") (pin "4") (pinfunction "SDI_4") (pintype "passive"))
    )
    (net (code "38") (name "Net-(D18-CKO)") (class "Default")
      (node (ref "D18") (pin "2") (pinfunction "CKO_2") (pintype "passive"))
      (node (ref "D19") (pin "5") (pinfunction "CKI_5") (pintype "passive"))
    )
    (net (code "39") (name "Net-(D18-SDO)") (class "Default")
      (node (ref "D18") (pin "3") (pinfunction "SDO_3") (pintype "passive"))
      (node (ref "D19") (pin "4") (pinfunction "SDI_4") (pintype "passive"))
    )
    (net (code "40") (name "Net-(D19-CKO)") (class "Default")
      (node (ref "D19") (pin "2") (pinfunction "CKO_2") (pintype "passive"))
      (node (ref "D20") (pin "5") (pinfunction "CKI_5") (pintype "passive"))
    )
    (net (code "41") (name "Net-(D19-SDO)") (class "Default")
      (node (ref "D19") (pin "3") (pinfunction "SDO_3") (pintype "passive"))
      (node (ref "D20") (pin "4") (pinfunction "SDI_4") (pintype "passive"))
    )
    (net (code "42") (name "Net-(D20-CKO)") (class "Default")
      (node (ref "D20") (pin "2") (pinfunction "CKO_2") (pintype "passive"))
      (node (ref "D21") (pin "5") (pinfunction "CKI_5") (pintype "passive"))
    )
    (net (code "43") (name "Net-(D20-SDO)") (class "Default")
      (node (ref "D20") (pin "3") (pinfunction "SDO_3") (pintype "passive"))
      (node (ref "D21") (pin "4") (pinfunction "SDI_4") (pintype "passive"))
    )
    (net (code "44") (name "Net-(D21-CKO)") (class "Default")
      (node (ref "D21") (pin "2") (pinfunction "CKO_2") (pintype "passive"))
      (node (ref "D22") (pin "5") (pinfunction "CKI_5") (pintype "passive"))
    )
    (net (code "45") (name "Net-(D21-SDO)") (class "Default")
      (node (ref "D21") (pin "3") (pinfunction "SDO_3") (pintype "passive"))
      (node (ref "D22") (pin "4") (pinfunction "SDI_4") (pintype "passive"))
    )
    (net (code "46") (name "Net-(D22-CKO)") (class "Default")
      (node (ref "D22") (pin "2") (pinfunction "CKO_2") (pintype "passive"))
      (node (ref "D23") (pin "5") (pinfunction "CKI_5") (pintype "passive"))
    )
    (net (code "47") (name "Net-(D22-SDO)") (class "Default")
      (node (ref "D22") (pin "3") (pinfunction "SDO_3") (pintype "passive"))
      (node (ref "D23") (pin "4") (pinfunction "SDI_4") (pintype "passive"))
    )
    (net (code "48") (name "Net-(D23-CKO)") (class "Default")
      (node (ref "D23") (pin "2") (pinfunction "CKO_2") (pintype "passive"))
      (node (ref "D24") (pin "5") (pinfunction "CKI_5") (pintype "passive"))
    )
    (net (code "49") (name "Net-(D23-SDO)") (class "Default")
      (node (ref "D23") (pin "3") (pinfunction "SDO_3") (pintype "passive"))
      (node (ref "D24") (pin "4") (pinfunction "SDI_4") (pintype "passive"))
    )
    (net (code "50") (name "Net-(D24-CKO)") (class "Default")
      (node (ref "D24") (pin "2") (pinfunction "CKO_2") (pintype "passive"))
      (node (ref "D25") (pin "5") (pinfunction "CKI_5") (pintype "passive"))
    )
    (net (code "51") (name "Net-(D24-SDO)") (class "Default")
      (node (ref "D24") (pin "3") (pinfunction "SDO_3") (pintype "passive"))
      (node (ref "D25") (pin "4") (pinfunction "SDI_4") (pintype "passive"))
    )
    (net (code "52") (name "Net-(D25-CKO)") (class "Default")
      (node (ref "D25") (pin "2") (pinfunction "CKO_2") (pintype "passive"))
      (node (ref "D26") (pin "5") (pinfunction "CKI_5") (pintype "passive"))
    )
    (net (code "53") (name "Net-(D25-SDO)") (class "Default")
      (node (ref "D25") (pin "3") (pinfunction "SDO_3") (pintype "passive"))
      (node (ref "D26") (pin "4") (pinfunction "SDI_4") (pintype "passive"))
    )
    (net (code "54") (name "Net-(D26-CKO)") (class "Default")
      (node (ref "D26") (pin "2") (pinfunction "CKO_2") (pintype "passive"))
      (node (ref "D27") (pin "5") (pinfunction "CKI_5") (pintype "passive"))
    )
    (net (code "55") (name "Net-(D26-SDO)") (class "Default")
      (node (ref "D26") (pin "3") (pinfunction "SDO_3") (pintype "passive"))
      (node (ref "D27") (pin "4") (pinfunction "SDI_4") (pintype "passive"))
    )
    (net (code "56") (name "Net-(D27-CKO)") (class "Default")
      (node (ref "D27") (pin "2") (pinfunction "CKO_2") (pintype "passive"))
      (node (ref "D28") (pin "5") (pinfunction "CKI_5") (pintype "passive"))
    )
    (net (code "57") (name "Net-(D27-SDO)") (class "Default")
      (node (ref "D27") (pin "3") (pinfunction "SDO_3") (pintype "passive"))
      (node (ref "D28") (pin "4") (pinfunction "SDI_4") (pintype "passive"))
    )
    (net (code "58") (name "Net-(D28-CKO)") (class "Default")
      (node (ref "D28") (pin "2") (pinfunction "CKO_2") (pintype "passive"))
      (node (ref "D29") (pin "5") (pinfunction "CKI_5") (pintype "passive"))
    )
    (net (code "59") (name "Net-(D28-SDO)") (class "Default")
      (node (ref "D28") (pin "3") (pinfunction "SDO_3") (pintype "passive"))
      (node (ref "D29") (pin "4") (pinfunction "SDI_4") (pintype "passive"))
    )
    (net (code "60") (name "Net-(D29-CKO)") (class "Default")
      (node (ref "D29") (pin "2") (pinfunction "CKO_2") (pintype "passive"))
      (node (ref "D30") (pin "5") (pinfunction "CKI_5") (pintype "passive"))
    )
    (net (code "61") (name "Net-(D29-SDO)") (class "Default")
      (node (ref "D29") (pin "3") (pinfunction "SDO_3") (pintype "passive"))
      (node (ref "D30") (pin "4") (pinfunction "SDI_4") (pintype "passive"))
    )
    (net (code "62") (name "Net-(D30-CKO)") (class "Default")
      (node (ref "D30") (pin "2") (pinfunction "CKO_2") (pintype "passive"))
      (node (ref "D31") (pin "5") (pinfunction "CKI_5") (pintype "passive"))
    )
    (net (code "63") (name "Net-(D30-SDO)") (class "Default")
      (node (ref "D30") (pin "3") (pinfunction "SDO_3") (pintype "passive"))
      (node (ref "D31") (pin "4") (pinfunction "SDI_4") (pintype "passive"))
    )
    (net (code "64") (name "Net-(D31-CKO)") (class "Default")
      (node (ref "D31") (pin "2") (pinfunction "CKO_2") (pintype "passive"))
      (node (ref "D32") (pin "5") (pinfunction "CKI_5") (pintype "passive"))
    )
    (net (code "65") (name "Net-(D31-SDO)") (class "Default")
      (node (ref "D31") (pin "3") (pinfunction "SDO_3") (pintype "passive"))
      (node (ref "D32") (pin "4") (pinfunction "SDI_4") (pintype "passive"))
    )
    (net (code "66") (name "Net-(D32-CKO)") (class "Default")
      (node (ref "D32") (pin "2") (pinfunction "CKO_2") (pintype "passive"))
      (node (ref "D33") (pin "5") (pinfunction "CKI_5") (pintype "passive"))
    )
    (net (code "67") (name "Net-(D32-SDO)") (class "Default")
      (node (ref "D32") (pin "3") (pinfunction "SDO_3") (pintype "passive"))
      (node (ref "D33") (pin "4") (pinfunction "SDI_4") (pintype "passive"))
    )
    (net (code "68") (name "Net-(D33-CKO)") (class "Default")
      (node (ref "D33") (pin "2") (pinfunction "CKO_2") (pintype "passive"))
      (node (ref "D34") (pin "5") (pinfunction "CKI_5") (pintype "passive"))
    )
    (net (code "69") (name "Net-(D33-SDO)") (class "Default")
      (node (ref "D33") (pin "3") (pinfunction "SDO_3") (pintype "passive"))
      (node (ref "D34") (pin "4") (pinfunction "SDI_4") (pintype "passive"))
    )
    (net (code "70") (name "Net-(D34-CKO)") (class "Default")
      (node (ref "D34") (pin "2") (pinfunction "CKO_2") (pintype "passive"))
      (node (ref "D35") (pin "5") (pinfunction "CKI_5") (pintype "passive"))
    )
    (net (code "71") (name "Net-(D34-SDO)") (class "Default")
      (node (ref "D34") (pin "3") (pinfunction "SDO_3") (pintype "passive"))
      (node (ref "D35") (pin "4") (pinfunction "SDI_4") (pintype "passive"))
    )
    (net (code "72") (name "Net-(D35-CKO)") (class "Default")
      (node (ref "D35") (pin "2") (pinfunction "CKO_2") (pintype "passive"))
      (node (ref "D36") (pin "5") (pinfunction "CKI_5") (pintype "passive"))
    )
    (net (code "73") (name "Net-(D35-SDO)") (class "Default")
      (node (ref "D35") (pin "3") (pinfunction "SDO_3") (pintype "passive"))
      (node (ref "D36") (pin "4") (pinfunction "SDI_4") (pintype "passive"))
    )
    (net (code "74") (name "Net-(D36-CKO)") (class "Default")
      (node (ref "D36") (pin "2") (pinfunction "CKO_2") (pintype "passive"))
      (node (ref "D37") (pin "5") (pinfunction "CKI_5") (pintype "passive"))
    )
    (net (code "75") (name "Net-(D36-SDO)") (class "Default")
      (node (ref "D36") (pin "3") (pinfunction "SDO_3") (pintype "passive"))
      (node (ref "D37") (pin "4") (pinfunction "SDI_4") (pintype "passive"))
    )
    (net (code "76") (name "Net-(D37-CKO)") (class "Default")
      (node (ref "D37") (pin "2") (pinfunction "CKO_2") (pintype "passive"))
      (node (ref "D38") (pin "5") (pinfunction "CKI_5") (pintype "passive"))
    )
    (net (code "77") (name "Net-(D37-SDO)") (class "Default")
      (node (ref "D37") (pin "3") (pinfunction "SDO_3") (pintype "passive"))
      (node (ref "D38") (pin "4") (pinfunction "SDI_4") (pintype "passive"))
    )
    (net (code "78") (name "Net-(D38-CKO)") (class "Default")
      (node (ref "D38") (pin "2") (pinfunction "CKO_2") (pintype "passive"))
      (node (ref "D39") (pin "5") (pinfunction "CKI_5") (pintype "passive"))
    )
    (net (code "79") (name "Net-(D38-SDO)") (class "Default")
      (node (ref "D38") (pin "3") (pinfunction "SDO_3") (pintype "passive"))
      (node (ref "D39") (pin "4") (pinfunction "SDI_4") (pintype "passive"))
    )
    (net (code "80") (name "Net-(D39-CKO)") (class "Default")
      (node (ref "D39") (pin "2") (pinfunction "CKO_2") (pintype "passive"))
      (node (ref "D40") (pin "5") (pinfunction "CKI_5") (pintype "passive"))
    )
    (net (code "81") (name "Net-(D39-SDO)") (class "Default")
      (node (ref "D39") (pin "3") (pinfunction "SDO_3") (pintype "passive"))
      (node (ref "D40") (pin "4") (pinfunction "SDI_4") (pintype "passive"))
    )
    (net (code "82") (name "Net-(D40-CKO)") (class "Default")
      (node (ref "D40") (pin "2") (pinfunction "CKO_2") (pintype "passive"))
      (node (ref "D41") (pin "5") (pinfunction "CKI_5") (pintype "passive"))
    )
    (net (code "83") (name "Net-(D40-SDO)") (class "Default")
      (node (ref "D40") (pin "3") (pinfunction "SDO_3") (pintype "passive"))
      (node (ref "D41") (pin "4") (pinfunction "SDI_4") (pintype "passive"))
    )
    (net (code "84") (name "Net-(D41-CKO)") (class "Default")
      (node (ref "D41") (pin "2") (pinfunction "CKO_2") (pintype "passive"))
      (node (ref "D42") (pin "5") (pinfunction "CKI_5") (pintype "passive"))
    )
    (net (code "85") (name "Net-(D41-SDO)") (class "Default")
      (node (ref "D41") (pin "3") (pinfunction "SDO_3") (pintype "passive"))
      (node (ref "D42") (pin "4") (pinfunction "SDI_4") (pintype "passive"))
    )
    (net (code "86") (name "Net-(D42-CKO)") (class "Default")
      (node (ref "D42") (pin "2") (pinfunction "CKO_2") (pintype "passive"))
      (node (ref "D43") (pin "5") (pinfunction "CKI_5") (pintype "passive"))
    )
    (net (code "87") (name "Net-(D42-SDO)") (class "Default")
      (node (ref "D42") (pin "3") (pinfunction "SDO_3") (pintype "passive"))
      (node (ref "D43") (pin "4") (pinfunction "SDI_4") (pintype "passive"))
    )
    (net (code "88") (name "Net-(D43-CKO)") (class "Default")
      (node (ref "D43") (pin "2") (pinfunction "CKO_2") (pintype "passive"))
      (node (ref "D44") (pin "5") (pinfunction "CKI_5") (pintype "passive"))
    )
    (net (code "89") (name "Net-(D43-SDO)") (class "Default")
      (node (ref "D43") (pin "3") (pinfunction "SDO_3") (pintype "passive"))
      (node (ref "D44") (pin "4") (pinfunction "SDI_4") (pintype "passive"))
    )
    (net (code "90") (name "Net-(D44-CKO)") (class "Default")
      (node (ref "D44") (pin "2") (pinfunction "CKO_2") (pintype "passive"))
      (node (ref "D45") (pin "5") (pinfunction "CKI_5") (pintype "passive"))
    )
    (net (code "91") (name "Net-(D44-SDO)") (class "Default")
      (node (ref "D44") (pin "3") (pinfunction "SDO_3") (pintype "passive"))
      (node (ref "D45") (pin "4") (pinfunction "SDI_4") (pintype "passive"))
    )
    (net (code "92") (name "Net-(D45-CKO)") (class "Default")
      (node (ref "D45") (pin "2") (pinfunction "CKO_2") (pintype "passive"))
      (node (ref "D46") (pin "5") (pinfunction "CKI_5") (pintype "passive"))
    )
    (net (code "93") (name "Net-(D45-SDO)") (class "Default")
      (node (ref "D45") (pin "3") (pinfunction "SDO_3") (pintype "passive"))
      (node (ref "D46") (pin "4") (pinfunction "SDI_4") (pintype "passive"))
    )
    (net (code "94") (name "Net-(D46-CKO)") (class "Default")
      (node (ref "D46") (pin "2") (pinfunction "CKO_2") (pintype "passive"))
      (node (ref "D47") (pin "5") (pinfunction "CKI_5") (pintype "passive"))
    )
    (net (code "95") (name "Net-(D46-SDO)") (class "Default")
      (node (ref "D46") (pin "3") (pinfunction "SDO_3") (pintype "passive"))
      (node (ref "D47") (pin "4") (pinfunction "SDI_4") (pintype "passive"))
    )
    (net (code "96") (name "Net-(D47-CKO)") (class "Default")
      (node (ref "D47") (pin "2") (pinfunction "CKO_2") (pintype "passive"))
      (node (ref "D48") (pin "5") (pinfunction "CKI_5") (pintype "passive"))
    )
    (net (code "97") (name "Net-(D47-SDO)") (class "Default")
      (node (ref "D47") (pin "3") (pinfunction "SDO_3") (pintype "passive"))
      (node (ref "D48") (pin "4") (pinfunction "SDI_4") (pintype "passive"))
    )
    (net (code "98") (name "Net-(D48-CKO)") (class "Default")
      (node (ref "D48") (pin "2") (pinfunction "CKO_2") (pintype "passive"))
      (node (ref "D49") (pin "5") (pinfunction "CKI_5") (pintype "passive"))
    )
    (net (code "99") (name "Net-(D48-SDO)") (class "Default")
      (node (ref "D48") (pin "3") (pinfunction "SDO_3") (pintype "passive"))
      (node (ref "D49") (pin "4") (pinfunction "SDI_4") (pintype "passive"))
    )
    (net (code "100") (name "Net-(D49-CKO)") (class "Default")
      (node (ref "D49") (pin "2") (pinfunction "CKO_2") (pintype "passive"))
      (node (ref "D50") (pin "5") (pinfunction "CKI_5") (pintype "passive"))
    )
    (net (code "101") (name "Net-(D49-SDO)") (class "Default")
      (node (ref "D49") (pin "3") (pinfunction "SDO_3") (pintype "passive"))
      (node (ref "D50") (pin "4") (pinfunction "SDI_4") (pintype "passive"))
    )
    (net (code "102") (name "Net-(D50-CKO)") (class "Default")
      (node (ref "D50") (pin "2") (pinfunction "CKO_2") (pintype "passive"))
      (node (ref "D51") (pin "5") (pinfunction "CKI_5") (pintype "passive"))
    )
    (net (code "103") (name "Net-(D50-SDO)") (class "Default")
      (node (ref "D50") (pin "3") (pinfunction "SDO_3") (pintype "passive"))
      (node (ref "D51") (pin "4") (pinfunction "SDI_4") (pintype "passive"))
    )
    (net (code "104") (name "Net-(D51-CKO)") (class "Default")
      (node (ref "D51") (pin "2") (pinfunction "CKO_2") (pintype "passive"))
      (node (ref "D52") (pin "5") (pinfunction "CKI_5") (pintype "passive"))
    )
    (net (code "105") (name "Net-(D51-SDO)") (class "Default")
      (node (ref "D51") (pin "3") (pinfunction "SDO_3") (pintype "passive"))
      (node (ref "D52") (pin "4") (pinfunction "SDI_4") (pintype "passive"))
    )
    (net (code "106") (name "Net-(D52-CKO)") (class "Default")
      (node (ref "D52") (pin "2") (pinfunction "CKO_2") (pintype "passive"))
      (node (ref "D53") (pin "5") (pinfunction "CKI_5") (pintype "passive"))
    )
    (net (code "107") (name "Net-(D52-SDO)") (class "Default")
      (node (ref "D52") (pin "3") (pinfunction "SDO_3") (pintype "passive"))
      (node (ref "D53") (pin "4") (pinfunction "SDI_4") (pintype "passive"))
    )
    (net (code "108") (name "Net-(D53-CKO)") (class "Default")
      (node (ref "D53") (pin "2") (pinfunction "CKO_2") (pintype "passive"))
      (node (ref "D54") (pin "5") (pinfunction "CKI_5") (pintype "passive"))
    )
    (net (code "109") (name "Net-(D53-SDO)") (class "Default")
      (node (ref "D53") (pin "3") (pinfunction "SDO_3") (pintype "passive"))
      (node (ref "D54") (pin "4") (pinfunction "SDI_4") (pintype "passive"))
    )
    (net (code "110") (name "Net-(D54-CKO)") (class "Default")
      (node (ref "D54") (pin "2") (pinfunction "CKO_2") (pintype "passive"))
      (node (ref "D55") (pin "5") (pinfunction "CKI_5") (pintype "passive"))
    )
    (net (code "111") (name "Net-(D54-SDO)") (class "Default")
      (node (ref "D54") (pin "3") (pinfunction "SDO_3") (pintype "passive"))
      (node (ref "D55") (pin "4") (pinfunction "SDI_4") (pintype "passive"))
    )
    (net (code "112") (name "Net-(D55-CKO)") (class "Default")
      (node (ref "D55") (pin "2") (pinfunction "CKO_2") (pintype "passive"))
      (node (ref "D56") (pin "5") (pinfunction "CKI_5") (pintype "passive"))
    )
    (net (code "113") (name "Net-(D55-SDO)") (class "Default")
      (node (ref "D55") (pin "3") (pinfunction "SDO_3") (pintype "passive"))
      (node (ref "D56") (pin "4") (pinfunction "SDI_4") (pintype "passive"))
    )
    (net (code "114") (name "Net-(D56-CKO)") (class "Default")
      (node (ref "D56") (pin "2") (pinfunction "CKO_2") (pintype "passive"))
      (node (ref "D57") (pin "5") (pinfunction "CKI_5") (pintype "passive"))
    )
    (net (code "115") (name "Net-(D56-SDO)") (class "Default")
      (node (ref "D56") (pin "3") (pinfunction "SDO_3") (pintype "passive"))
      (node (ref "D57") (pin "4") (pinfunction "SDI_4") (pintype "passive"))
    )
    (net (code "116") (name "Net-(D57-CKO)") (class "Default")
      (node (ref "D57") (pin "2") (pinfunction "CKO_2") (pintype "passive"))
      (node (ref "D58") (pin "5") (pinfunction "CKI_5") (pintype "passive"))
    )
    (net (code "117") (name "Net-(D57-SDO)") (class "Default")
      (node (ref "D57") (pin "3") (pinfunction "SDO_3") (pintype "passive"))
      (node (ref "D58") (pin "4") (pinfunction "SDI_4") (pintype "passive"))
    )
    (net (code "118") (name "Net-(D58-CKO)") (class "Default")
      (node (ref "D58") (pin "2") (pinfunction "CKO_2") (pintype "passive"))
      (node (ref "D59") (pin "5") (pinfunction "CKI_5") (pintype "passive"))
    )
    (net (code "119") (name "Net-(D58-SDO)") (class "Default")
      (node (ref "D58") (pin "3") (pinfunction "SDO_3") (pintype "passive"))
      (node (ref "D59") (pin "4") (pinfunction "SDI_4") (pintype "passive"))
    )
    (net (code "120") (name "Net-(D59-CKO)") (class "Default")
      (node (ref "D59") (pin "2") (pinfunction "CKO_2") (pintype "passive"))
      (node (ref "D60") (pin "5") (pinfunction "CKI_5") (pintype "passive"))
    )
    (net (code "121") (name "Net-(D59-SDO)") (class "Default")
      (node (ref "D59") (pin "3") (pinfunction "SDO_3") (pintype "passive"))
      (node (ref "D60") (pin "4") (pinfunction "SDI_4") (pintype "passive"))
    )
    (net (code "122") (name "Net-(D60-CKO)") (class "Default")
      (node (ref "D60") (pin "2") (pinfunction "CKO_2") (pintype "passive"))
      (node (ref "D61") (pin "5") (pinfunction "CKI_5") (pintype "passive"))
    )
    (net (code "123") (name "Net-(D60-SDO)") (class "Default")
      (node (ref "D60") (pin "3") (pinfunction "SDO_3") (pintype "passive"))
      (node (ref "D61") (pin "4") (pinfunction "SDI_4") (pintype "passive"))
    )
    (net (code "124") (name "Net-(D61-CKO)") (class "Default")
      (node (ref "D61") (pin "2") (pinfunction "CKO_2") (pintype "passive"))
      (node (ref "D62") (pin "5") (pinfunction "CKI_5") (pintype "passive"))
    )
    (net (code "125") (name "Net-(D61-SDO)") (class "Default")
      (node (ref "D61") (pin "3") (pinfunction "SDO_3") (pintype "passive"))
      (node (ref "D62") (pin "4") (pinfunction "SDI_4") (pintype "passive"))
    )
    (net (code "126") (name "Net-(D62-CKO)") (class "Default")
      (node (ref "D62") (pin "2") (pinfunction "CKO_2") (pintype "passive"))
      (node (ref "D63") (pin "5") (pinfunction "CKI_5") (pintype "passive"))
    )
    (net (code "127") (name "Net-(D62-SDO)") (class "Default")
      (node (ref "D62") (pin "3") (pinfunction "SDO_3") (pintype "passive"))
      (node (ref "D63") (pin "4") (pinfunction "SDI_4") (pintype "passive"))
    )
    (net (code "128") (name "Net-(D63-CKO)") (class "Default")
      (node (ref "D63") (pin "2") (pinfunction "CKO_2") (pintype "passive"))
      (node (ref "D64") (pin "5") (pinfunction "CKI_5") (pintype "passive"))
    )
    (net (code "129") (name "Net-(D63-SDO)") (class "Default")
      (node (ref "D63") (pin "3") (pinfunction "SDO_3") (pintype "passive"))
      (node (ref "D64") (pin "4") (pinfunction "SDI_4") (pintype "passive"))
    )
    (net (code "130") (name "Net-(D64-CKO)") (class "Default")
      (node (ref "D64") (pin "2") (pinfunction "CKO_2") (pintype "passive"))
      (node (ref "D65") (pin "5") (pinfunction "CKI_5") (pintype "passive"))
    )
    (net (code "131") (name "Net-(D64-SDO)") (class "Default")
      (node (ref "D64") (pin "3") (pinfunction "SDO_3") (pintype "passive"))
      (node (ref "D65") (pin "4") (pinfunction "SDI_4") (pintype "passive"))
    )
    (net (code "132") (name "Net-(D65-CKO)") (class "Default")
      (node (ref "D65") (pin "2") (pinfunction "CKO_2") (pintype "passive"))
      (node (ref "D66") (pin "5") (pinfunction "CKI_5") (pintype "passive"))
    )
    (net (code "133") (name "Net-(D65-SDO)") (class "Default")
      (node (ref "D65") (pin "3") (pinfunction "SDO_3") (pintype "passive"))
      (node (ref "D66") (pin "4") (pinfunction "SDI_4") (pintype "passive"))
    )
    (net (code "134") (name "Net-(D66-CKO)") (class "Default")
      (node (ref "D66") (pin "2") (pinfunction "CKO_2") (pintype "passive"))
      (node (ref "D67") (pin "5") (pinfunction "CKI_5") (pintype "passive"))
    )
    (net (code "135") (name "Net-(D66-SDO)") (class "Default")
      (node (ref "D66") (pin "3") (pinfunction "SDO_3") (pintype "passive"))
      (node (ref "D67") (pin "4") (pinfunction "SDI_4") (pintype "passive"))
    )
    (net (code "136") (name "Net-(D67-CKO)") (class "Default")
      (node (ref "D67") (pin "2") (pinfunction "CKO_2") (pintype "passive"))
      (node (ref "D68") (pin "5") (pinfunction "CKI_5") (pintype "passive"))
    )
    (net (code "137") (name "Net-(D67-SDO)") (class "Default")
      (node (ref "D67") (pin "3") (pinfunction "SDO_3") (pintype "passive"))
      (node (ref "D68") (pin "4") (pinfunction "SDI_4") (pintype "passive"))
    )
    (net (code "138") (name "Net-(D68-CKO)") (class "Default")
      (node (ref "D68") (pin "2") (pinfunction "CKO_2") (pintype "passive"))
      (node (ref "D69") (pin "5") (pinfunction "CKI_5") (pintype "passive"))
    )
    (net (code "139") (name "Net-(D68-SDO)") (class "Default")
      (node (ref "D68") (pin "3") (pinfunction "SDO_3") (pintype "passive"))
      (node (ref "D69") (pin "4") (pinfunction "SDI_4") (pintype "passive"))
    )
    (net (code "140") (name "Net-(D69-CKO)") (class "Default")
      (node (ref "D69") (pin "2") (pinfunction "CKO_2") (pintype "passive"))
      (node (ref "D70") (pin "5") (pinfunction "CKI_5") (pintype "passive"))
    )
    (net (code "141") (name "Net-(D69-SDO)") (class "Default")
      (node (ref "D69") (pin "3") (pinfunction "SDO_3") (pintype "passive"))
      (node (ref "D70") (pin "4") (pinfunction "SDI_4") (pintype "passive"))
    )
    (net (code "142") (name "Net-(D70-CKO)") (class "Default")
      (node (ref "D70") (pin "2") (pinfunction "CKO_2") (pintype "passive"))
      (node (ref "D71") (pin "5") (pinfunction "CKI_5") (pintype "passive"))
    )
    (net (code "143") (name "Net-(D70-SDO)") (class "Default")
      (node (ref "D70") (pin "3") (pinfunction "SDO_3") (pintype "passive"))
      (node (ref "D71") (pin "4") (pinfunction "SDI_4") (pintype "passive"))
    )
    (net (code "144") (name "Net-(D71-CKO)") (class "Default")
      (node (ref "D71") (pin "2") (pinfunction "CKO_2") (pintype "passive"))
      (node (ref "D72") (pin "5") (pinfunction "CKI_5") (pintype "passive"))
    )
    (net (code "145") (name "Net-(D71-SDO)") (class "Default")
      (node (ref "D71") (pin "3") (pinfunction "SDO_3") (pintype "passive"))
      (node (ref "D72") (pin "4") (pinfunction "SDI_4") (pintype "passive"))
    )
    (net (code "146") (name "Net-(D72-CKO)") (class "Default")
      (node (ref "D72") (pin "2") (pinfunction "CKO_2") (pintype "passive"))
      (node (ref "D73") (pin "5") (pinfunction "CKI_5") (pintype "passive"))
    )
    (net (code "147") (name "Net-(D72-SDO)") (class "Default")
      (node (ref "D72") (pin "3") (pinfunction "SDO_3") (pintype "passive"))
      (node (ref "D73") (pin "4") (pinfunction "SDI_4") (pintype "passive"))
    )
    (net (code "148") (name "Net-(D73-CKO)") (class "Default")
      (node (ref "D73") (pin "2") (pinfunction "CKO_2") (pintype "passive"))
      (node (ref "D74") (pin "5") (pinfunction "CKI_5") (pintype "passive"))
    )
    (net (code "149") (name "Net-(D73-SDO)") (class "Default")
      (node (ref "D73") (pin "3") (pinfunction "SDO_3") (pintype "passive"))
      (node (ref "D74") (pin "4") (pinfunction "SDI_4") (pintype "passive"))
    )
    (net (code "150") (name "Net-(D74-CKO)") (class "Default")
      (node (ref "D74") (pin "2") (pinfunction "CKO_2") (pintype "passive"))
      (node (ref "D75") (pin "5") (pinfunction "CKI_5") (pintype "passive"))
    )
    (net (code "151") (name "Net-(D74-SDO)") (class "Default")
      (node (ref "D74") (pin "3") (pinfunction "SDO_3") (pintype "passive"))
      (node (ref "D75") (pin "4") (pinfunction "SDI_4") (pintype "passive"))
    )
    (net (code "152") (name "Net-(D75-CKO)") (class "Default")
      (node (ref "D75") (pin "2") (pinfunction "CKO_2") (pintype "passive"))
      (node (ref "D76") (pin "5") (pinfunction "CKI_5") (pintype "passive"))
    )
    (net (code "153") (name "Net-(D75-SDO)") (class "Default")
      (node (ref "D75") (pin "3") (pinfunction "SDO_3") (pintype "passive"))
      (node (ref "D76") (pin "4") (pinfunction "SDI_4") (pintype "passive"))
    )
    (net (code "154") (name "Net-(D76-CKO)") (class "Default")
      (node (ref "D76") (pin "2") (pinfunction "CKO_2") (pintype "passive"))
      (node (ref "D77") (pin "5") (pinfunction "CKI_5") (pintype "passive"))
    )
    (net (code "155") (name "Net-(D76-SDO)") (class "Default")
      (node (ref "D76") (pin "3") (pinfunction "SDO_3") (pintype "passive"))
      (node (ref "D77") (pin "4") (pinfunction "SDI_4") (pintype "passive"))
    )
    (net (code "156") (name "Net-(D77-CKO)") (class "Default")
      (node (ref "D77") (pin "2") (pinfunction "CKO_2") (pintype "passive"))
      (node (ref "D78") (pin "5") (pinfunction "CKI_5") (pintype "passive"))
    )
    (net (code "157") (name "Net-(D77-SDO)") (class "Default")
      (node (ref "D77") (pin "3") (pinfunction "SDO_3") (pintype "passive"))
      (node (ref "D78") (pin "4") (pinfunction "SDI_4") (pintype "passive"))
    )
    (net (code "158") (name "Net-(D78-CKO)") (class "Default")
      (node (ref "D78") (pin "2") (pinfunction "CKO_2") (pintype "passive"))
      (node (ref "D79") (pin "5") (pinfunction "CKI_5") (pintype "passive"))
    )
    (net (code "159") (name "Net-(D78-SDO)") (class "Default")
      (node (ref "D78") (pin "3") (pinfunction "SDO_3") (pintype "passive"))
      (node (ref "D79") (pin "4") (pinfunction "SDI_4") (pintype "passive"))
    )
    (net (code "160") (name "Net-(D79-CKO)") (class "Default")
      (node (ref "D79") (pin "2") (pinfunction "CKO_2") (pintype "passive"))
      (node (ref "D80") (pin "5") (pinfunction "CKI_5") (pintype "passive"))
    )
    (net (code "161") (name "Net-(D79-SDO)") (class "Default")
      (node (ref "D79") (pin "3") (pinfunction "SDO_3") (pintype "passive"))
      (node (ref "D80") (pin "4") (pinfunction "SDI_4") (pintype "passive"))
    )
    (net (code "162") (name "Net-(D80-CKO)") (class "Default")
      (node (ref "D80") (pin "2") (pinfunction "CKO_2") (pintype "passive"))
      (node (ref "D81") (pin "5") (pinfunction "CKI_5") (pintype "passive"))
    )
    (net (code "163") (name "Net-(D80-SDO)") (class "Default")
      (node (ref "D80") (pin "3") (pinfunction "SDO_3") (pintype "passive"))
      (node (ref "D81") (pin "4") (pinfunction "SDI_4") (pintype "passive"))
    )
    (net (code "164") (name "Net-(D81-CKO)") (class "Default")
      (node (ref "D81") (pin "2") (pinfunction "CKO_2") (pintype "passive"))
      (node (ref "D82") (pin "5") (pinfunction "CKI_5") (pintype "passive"))
    )
    (net (code "165") (name "Net-(D81-SDO)") (class "Default")
      (node (ref "D81") (pin "3") (pinfunction "SDO_3") (pintype "passive"))
      (node (ref "D82") (pin "4") (pinfunction "SDI_4") (pintype "passive"))
    )
    (net (code "166") (name "Net-(D82-CKO)") (class "Default")
      (node (ref "D82") (pin "2") (pinfunction "CKO_2") (pintype "passive"))
      (node (ref "D83") (pin "5") (pinfunction "CKI_5") (pintype "passive"))
    )
    (net (code "167") (name "Net-(D82-SDO)") (class "Default")
      (node (ref "D82") (pin "3") (pinfunction "SDO_3") (pintype "passive"))
      (node (ref "D83") (pin "4") (pinfunction "SDI_4") (pintype "passive"))
    )
    (net (code "168") (name "VDD") (class "Default")
      (node (ref "C11") (pin "2") (pinfunction "2_2") (pintype "passive"))
      (node (ref "C12") (pin "2") (pinfunction "2_2") (pintype "passive"))
      (node (ref "C13") (pin "2") (pinfunction "2_2") (pintype "passive"))
      (node (ref "C14") (pin "2") (pinfunction "2_2") (pintype "passive"))
      (node (ref "C15") (pin "2") (pinfunction "2_2") (pintype "passive"))
      (node (ref "C16") (pin "2") (pinfunction "2_2") (pintype "passive"))
      (node (ref "C17") (pin "2") (pinfunction "2_2") (pintype "passive"))
      (node (ref "C18") (pin "2") (pinfunction "2_2") (pintype "passive"))
      (node (ref "C19") (pin "2") (pinfunction "2_2") (pintype "passive"))
      (node (ref "C20") (pin "2") (pinfunction "2_2") (pintype "passive"))
      (node (ref "C21") (pin "2") (pinfunction "2_2") (pintype "passive"))
      (node (ref "C22") (pin "2") (pinfunction "2_2") (pintype "passive"))
      (node (ref "C23") (pin "2") (pinfunction "2_2") (pintype "passive"))
      (node (ref "C24") (pin "2") (pinfunction "2_2") (pintype "passive"))
      (node (ref "C25") (pin "2") (pinfunction "2_2") (pintype "passive"))
      (node (ref "C26") (pin "2") (pinfunction "2_2") (pintype "passive"))
      (node (ref "C27") (pin "2") (pinfunction "2_2") (pintype "passive"))
      (node (ref "C28") (pin "2") (pinfunction "2_2") (pintype "passive"))
      (node (ref "C29") (pin "2") (pinfunction "2_2") (pintype "passive"))
      (node (ref "D1") (pin "1") (pinfunction "VDD_1") (pintype "passive"))
      (node (ref "D10") (pin "1") (pinfunction "VDD_1") (pintype "passive"))
      (node (ref "D11") (pin "1") (pinfunction "VDD_1") (pintype "passive"))
      (node (ref "D12") (pin "1") (pinfunction "VDD_1") (pintype "passive"))
      (node (ref "D13") (pin "1") (pinfunction "VDD_1") (pintype "passive"))
      (node (ref "D14") (pin "1") (pinfunction "VDD_1") (pintype "passive"))
      (node (ref "D15") (pin "1") (pinfunction "VDD_1") (pintype "passive"))
      (node (ref "D16") (pin "1") (pinfunction "VDD_1") (pintype "passive"))
      (node (ref "D17") (pin "1") (pinfunction "VDD_1") (pintype "passive"))
      (node (ref "D18") (pin "1") (pinfunction "VDD_1") (pintype "passive"))
      (node (ref "D19") (pin "1") (pinfunction "VDD_1") (pintype "passive"))
      (node (ref "D2") (pin "1") (pinfunction "VDD_1") (pintype "passive"))
      (node (ref "D20") (pin "1") (pinfunction "VDD_1") (pintype "passive"))
      (node (ref "D21") (pin "1") (pinfunction "VDD_1") (pintype "passive"))
      (node (ref "D22") (pin "1") (pinfunction "VDD_1") (pintype "passive"))
      (node (ref "D23") (pin "1") (pinfunction "VDD_1") (pintype "passive"))
      (node (ref "D24") (pin "1") (pinfunction "VDD_1") (pintype "passive"))
      (node (ref "D25") (pin "1") (pinfunction "VDD_1") (pintype "passive"))
      (node (ref "D26") (pin "1") (pinfunction "VDD_1") (pintype "passive"))
      (node (ref "D27") (pin "1") (pinfunction "VDD_1") (pintype "passive"))
      (node (ref "D28") (pin "1") (pinfunction "VDD_1") (pintype "passive"))
      (node (ref "D29") (pin "1") (pinfunction "VDD_1") (pintype "passive"))
      (node (ref "D3") (pin "1") (pinfunction "VDD_1") (pintype "passive"))
      (node (ref "D30") (pin "1") (pinfunction "VDD_1") (pintype "passive"))
      (node (ref "D31") (pin "1") (pinfunction "VDD_1") (pintype "passive"))
      (node (ref "D32") (pin "1") (pinfunction "VDD_1") (pintype "passive"))
      (node (ref "D33") (pin "1") (pinfunction "VDD_1") (pintype "passive"))
      (node (ref "D34") (pin "1") (pinfunction "VDD_1") (pintype "passive"))
      (node (ref "D35") (pin "1") (pinfunction "VDD_1") (pintype "passive"))
      (node (ref "D36") (pin "1") (pinfunction "VDD_1") (pintype "passive"))
      (node (ref "D37") (pin "1") (pinfunction "VDD_1") (pintype "passive"))
      (node (ref "D38") (pin "1") (pinfunction "VDD_1") (pintype "passive"))
      (node (ref "D39") (pin "1") (pinfunction "VDD_1") (pintype "passive"))
      (node (ref "D4") (pin "1") (pinfunction "VDD_1") (pintype "passive"))
      (node (ref "D40") (pin "1") (pinfunction "VDD_1") (pintype "passive"))
      (node (ref "D41") (pin "1") (pinfunction "VDD_1") (pintype "passive"))
      (node (ref "D42") (pin "1") (pinfunction "VDD_1") (pintype "passive"))
      (node (ref "D43") (pin "1") (pinfunction "VDD_1") (pintype "passive"))
      (node (ref "D44") (pin "1") (pinfunction "VDD_1") (pintype "passive"))
      (node (ref "D45") (pin "1") (pinfunction "VDD_1") (pintype "passive"))
      (node (ref "D46") (pin "1") (pinfunction "VDD_1") (pintype "passive"))
      (node (ref "D47") (pin "1") (pinfunction "VDD_1") (pintype "passive"))
      (node (ref "D48") (pin "1") (pinfunction "VDD_1") (pintype "passive"))
      (node (ref "D49") (pin "1") (pinfunction "VDD_1") (pintype "passive"))
      (node (ref "D5") (pin "1") (pinfunction "VDD_1") (pintype "passive"))
      (node (ref "D50") (pin "1") (pinfunction "VDD_1") (pintype "passive"))
      (node (ref "D51") (pin "1") (pinfunction "VDD_1") (pintype "passive"))
      (node (ref "D52") (pin "1") (pinfunction "VDD_1") (pintype "passive"))
      (node (ref "D53") (pin "1") (pinfunction "VDD_1") (pintype "passive"))
      (node (ref "D54") (pin "1") (pinfunction "VDD_1") (pintype "passive"))
      (node (ref "D55") (pin "1") (pinfunction "VDD_1") (pintype "passive"))
      (node (ref "D56") (pin "1") (pinfunction "VDD_1") (pintype "passive"))
      (node (ref "D57") (pin "1") (pinfunction "VDD_1") (pintype "passive"))
      (node (ref "D58") (pin "1") (pinfunction "VDD_1") (pintype "passive"))
      (node (ref "D59") (pin "1") (pinfunction "VDD_1") (pintype "passive"))
      (node (ref "D6") (pin "1") (pinfunction "VDD_1") (pintype "passive"))
      (node (ref "D60") (pin "1") (pinfunction "VDD_1") (pintype "passive"))
      (node (ref "D61") (pin "1") (pinfunction "VDD_1") (pintype "passive"))
      (node (ref "D62") (pin "1") (pinfunction "VDD_1") (pintype "passive"))
      (node (ref "D63") (pin "1") (pinfunction "VDD_1") (pintype "passive"))
      (node (ref "D64") (pin "1") (pinfunction "VDD_1") (pintype "passive"))
      (node (ref "D65") (pin "1") (pinfunction "VDD_1") (pintype "passive"))
      (node (ref "D66") (pin "1") (pinfunction "VDD_1") (pintype "passive"))
      (node (ref "D67") (pin "1") (pinfunction "VDD_1") (pintype "passive"))
      (node (ref "D68") (pin "1") (pinfunction "VDD_1") (pintype "passive"))
      (node (ref "D69") (pin "1") (pinfunction "VDD_1") (pintype "passive"))
      (node (ref "D7") (pin "1") (pinfunction "VDD_1") (pintype "passive"))
      (node (ref "D70") (pin "1") (pinfunction "VDD_1") (pintype "passive"))
      (node (ref "D71") (pin "1") (pinfunction "VDD_1") (pintype "passive"))
      (node (ref "D72") (pin "1") (pinfunction "VDD_1") (pintype "passive"))
      (node (ref "D73") (pin "1") (pinfunction "VDD_1") (pintype "passive"))
      (node (ref "D74") (pin "1") (pinfunction "VDD_1") (pintype "passive"))
      (node (ref "D75") (pin "1") (pinfunction "VDD_1") (pintype "passive"))
      (node (ref "D76") (pin "1") (pinfunction "VDD_1") (pintype "passive"))
      (node (ref "D77") (pin "1") (pinfunction "VDD_1") (pintype "passive"))
      (node (ref "D78") (pin "1") (pinfunction "VDD_1") (pintype "passive"))
      (node (ref "D79") (pin "1") (pinfunction "VDD_1") (pintype "passive"))
      (node (ref "D8") (pin "1") (pinfunction "VDD_1") (pintype "passive"))
      (node (ref "D80") (pin "1") (pinfunction "VDD_1") (pintype "passive"))
      (node (ref "D81") (pin "1") (pinfunction "VDD_1") (pintype "passive"))
      (node (ref "D82") (pin "1") (pinfunction "VDD_1") (pintype "passive"))
      (node (ref "D83") (pin "1") (pinfunction "VDD_1") (pintype "passive"))
      (node (ref "D9") (pin "1") (pinfunction "VDD_1") (pintype "passive"))
    )
    (net (code "169") (name "unconnected-(D83-CKO-Pad2)") (class "Default")
      (node (ref "D83") (pin "2") (pinfunction "CKO_2") (pintype "passive"))
    )
    (net (code "170") (name "unconnected-(D83-SDO-Pad3)") (class "Default")
      (node (ref "D83") (pin "3") (pinfunction "SDO_3") (pintype "passive"))
    )
  )
)
